# Sheet1.net
KiCad netlist of a schematic drawn in Altium Designer
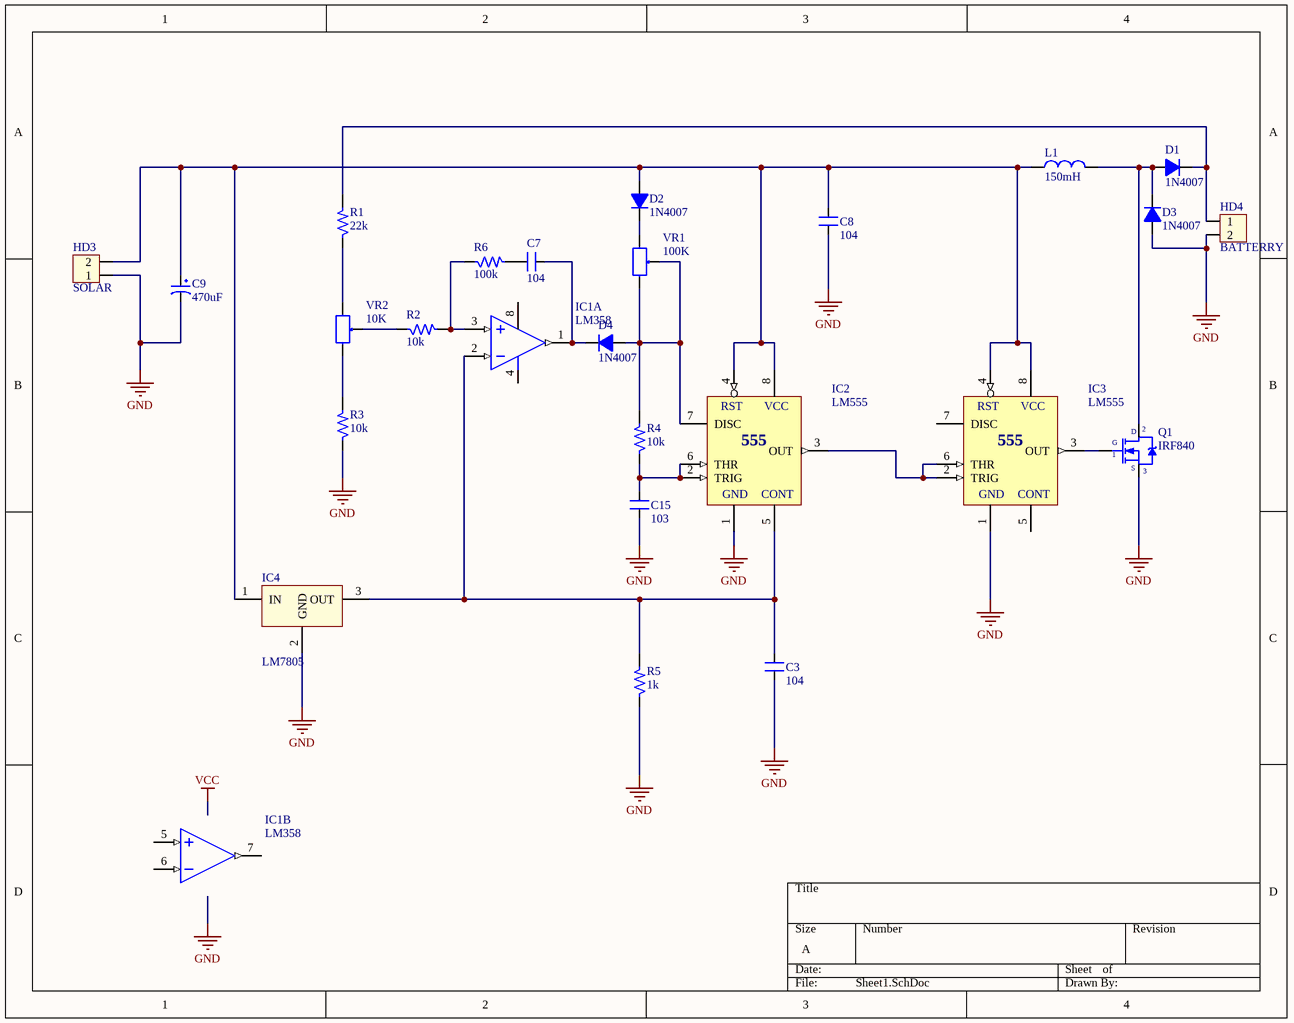
[diagram p0: Sheet1.SchDoc]

(export (version "E")
  (design (tool "Eeschema 10.0.6"))
  (components
    (comp (ref "C3")
      (value "104")
      (footprint "CN2")
      (description "Cap np 104 => 105pF")
      (libsource (lib "syhaunguyen") (part "CN2"))
    )
    (comp (ref "C7")
      (value "104")
      (footprint "CN1")
      (description "Cap np  1pF - 472pF")
      (libsource (lib "syhaunguyen") (part "CN1"))
    )
    (comp (ref "C8")
      (value "104")
      (footprint "CN1")
      (description "Cap np  1pF - 472pF")
      (libsource (lib "syhaunguyen") (part "CN1"))
    )
    (comp (ref "C9")
      (value "470uF")
      (footprint "CP1/2")
      (description "Cap P  0,1uF < 22uF , 16 - 50V")
      (libsource (lib "syhaunguyen") (part "CP1"))
    )
    (comp (ref "C15")
      (value "103")
      (footprint "CN1")
      (description "Cap np  1pF - 472pF")
      (libsource (lib "syhaunguyen") (part "CN1"))
    )
    (comp (ref "D1")
      (value "1N4007")
      (footprint "D1A")
      (description "Diode 1A")
      (libsource (lib "syhaunguyen") (part "D1A"))
    )
    (comp (ref "D2")
      (value "1N4007")
      (footprint "D1A")
      (description "Diode 1A")
      (libsource (lib "syhaunguyen") (part "D1A"))
    )
    (comp (ref "D3")
      (value "1N4007")
      (footprint "D1A")
      (description "Diode 1A")
      (libsource (lib "syhaunguyen") (part "D1A"))
    )
    (comp (ref "D4")
      (value "1N4007")
      (footprint "D1A")
      (description "Diode 1A")
      (libsource (lib "syhaunguyen") (part "D1A"))
    )
    (comp (ref "HD3")
      (value "SOLAR")
      (footprint "HED2")
      (description "Header 2 (Green)")
      (libsource (lib "syhaunguyen") (part "Hed2"))
    )
    (comp (ref "HD4")
      (value "BATTERRY")
      (footprint "HED2")
      (description "Header 2 (Green)")
      (libsource (lib "") (part "Hed2_1"))
    )
    (comp (ref "IC1")
      (value "LM358")
      (footprint "DIP8/W0.3")
      (description "Low-Power Dual Operational Amplifier")
      (libsource (lib "syhaunguyen") (part "LM358"))
    )
    (comp (ref "IC2")
      (value "LM555")
      (footprint "DIP8/W0.3")
      (description "Timer")
      (libsource (lib "syhaunguyen") (part "LM555"))
    )
    (comp (ref "IC3")
      (value "LM555")
      (footprint "DIP8/W0.3")
      (description "Timer")
      (libsource (lib "syhaunguyen") (part "LM555"))
    )
    (comp (ref "IC4")
      (value "LM7805")
      (footprint "QTO-220")
      (description "On ap +, from + 5 to + 24VDC")
      (libsource (lib "syhaunguyen") (part "LM78xx"))
    )
    (comp (ref "L1")
      (value "150mH")
      (footprint "L/0.4")
      (description "Inductor")
      (libsource (lib "syhaunguyen") (part "L1"))
    )
    (comp (ref "Q1")
      (value "IRF840")
      (footprint "QTO-220")
      (description "MOSFET N - CHANNEL 500V - 0.75 - 8A - TO-220")
      (libsource (lib "syhaunguyen") (part "IRF840"))
    )
    (comp (ref "R1")
      (value "22k")
      (footprint "SM-RES-1206")
      (description "Resistor 1/4W")
      (libsource (lib "syhaunguyen") (part "R"))
    )
    (comp (ref "R2")
      (value "10k")
      (footprint "SM-RES-1206")
      (description "Resistor 1/4W")
      (libsource (lib "syhaunguyen") (part "R"))
    )
    (comp (ref "R3")
      (value "10k")
      (footprint "SM-RES-1206")
      (description "Resistor 1/4W")
      (libsource (lib "syhaunguyen") (part "R"))
    )
    (comp (ref "R4")
      (value "10k")
      (footprint "SM-RES-1206")
      (description "Resistor 1/4W")
      (libsource (lib "syhaunguyen") (part "R"))
    )
    (comp (ref "R5")
      (value "1k")
      (footprint "SM-RES-1206")
      (description "Resistor 1/4W")
      (libsource (lib "syhaunguyen") (part "R"))
    )
    (comp (ref "R6")
      (value "100k")
      (footprint "SM-RES-1206")
      (description "Resistor 1/4W")
      (libsource (lib "syhaunguyen") (part "R"))
    )
    (comp (ref "VR1")
      (value "100K")
      (footprint "VR")
      (description "Var Resistor")
      (libsource (lib "syhaunguyen") (part "VR"))
    )
    (comp (ref "VR2")
      (value "10K")
      (footprint "VR")
      (description "Var Resistor")
      (libsource (lib "syhaunguyen") (part "VR"))
    )
  )
  (nets
    (net (code "1") (name "GND") (class "Default")
      (node (ref "C15") (pin "1") (pinfunction "1_1") (pintype "passive"))
      (node (ref "C3") (pin "1") (pinfunction "1_1") (pintype "passive"))
      (node (ref "C8") (pin "1") (pinfunction "1_1") (pintype "passive"))
      (node (ref "C9") (pin "2") (pinfunction "2_2") (pintype "passive"))
      (node (ref "D3") (pin "1") (pinfunction "A_1") (pintype "passive"))
      (node (ref "HD3") (pin "1") (pinfunction "1_1") (pintype "passive"))
      (node (ref "HD4") (pin "2") (pinfunction "2_2") (pintype "passive"))
      (node (ref "IC2") (pin "1") (pinfunction "GND_1") (pintype "power_in"))
      (node (ref "IC3") (pin "1") (pinfunction "GND_1") (pintype "power_in"))
      (node (ref "IC4") (pin "2") (pinfunction "GND_2") (pintype "passive"))
      (node (ref "Q1") (pin "3") (pinfunction "S_3") (pintype "passive"))
      (node (ref "R3") (pin "1") (pinfunction "1_1") (pintype "passive"))
      (node (ref "R5") (pin "1") (pinfunction "1_1") (pintype "passive"))
    )
    (net (code "2") (name "Net-(C7-Pad2)") (class "Default")
      (node (ref "C7") (pin "2") (pinfunction "2_2") (pintype "passive"))
      (node (ref "R6") (pin "2") (pinfunction "2_2") (pintype "passive"))
    )
    (net (code "3") (name "Net-(D1-A)") (class "Default")
      (node (ref "D1") (pin "1") (pinfunction "A_1") (pintype "passive"))
      (node (ref "D3") (pin "2") (pinfunction "K_2") (pintype "passive"))
      (node (ref "L1") (pin "2") (pinfunction "2_2") (pintype "passive"))
      (node (ref "Q1") (pin "2") (pinfunction "D_2") (pintype "passive"))
    )
    (net (code "4") (name "Net-(D1-K)") (class "Default")
      (node (ref "D1") (pin "2") (pinfunction "K_2") (pintype "passive"))
      (node (ref "HD4") (pin "1") (pinfunction "1_1") (pintype "passive"))
      (node (ref "R1") (pin "2") (pinfunction "2_2") (pintype "passive"))
    )
    (net (code "5") (name "Net-(D2-A)") (class "Default")
      (node (ref "C8") (pin "2") (pinfunction "2_2") (pintype "passive"))
      (node (ref "C9") (pin "1") (pinfunction "1_1") (pintype "passive"))
      (node (ref "D2") (pin "1") (pinfunction "A_1") (pintype "passive"))
      (node (ref "HD3") (pin "2") (pinfunction "2_2") (pintype "passive"))
      (node (ref "IC2") (pin "4") (pinfunction "RST_4") (pintype "input"))
      (node (ref "IC2") (pin "8") (pinfunction "VCC_8") (pintype "power_in"))
      (node (ref "IC3") (pin "4") (pinfunction "RST_4") (pintype "input"))
      (node (ref "IC3") (pin "8") (pinfunction "VCC_8") (pintype "power_in"))
      (node (ref "IC4") (pin "1") (pinfunction "IN_1") (pintype "passive"))
      (node (ref "L1") (pin "1") (pinfunction "1_1") (pintype "passive"))
    )
    (net (code "6") (name "Net-(D2-K)") (class "Default")
      (node (ref "D2") (pin "2") (pinfunction "K_2") (pintype "passive"))
      (node (ref "VR1") (pin "1") (pinfunction "1_1") (pintype "passive"))
    )
    (net (code "7") (name "Net-(D4-A)") (class "Default")
      (node (ref "D4") (pin "1") (pinfunction "A_1") (pintype "passive"))
      (node (ref "IC2") (pin "7") (pinfunction "DISC_7") (pintype "open_collector"))
      (node (ref "R4") (pin "2") (pinfunction "2_2") (pintype "passive"))
      (node (ref "VR1") (pin "2") (pinfunction "2_2") (pintype "passive"))
      (node (ref "VR1") (pin "3") (pinfunction "3_3") (pintype "passive"))
    )
    (net (code "8") (name "Net-(D4-K)") (class "Default")
      (node (ref "C7") (pin "1") (pinfunction "1_1") (pintype "passive"))
      (node (ref "D4") (pin "2") (pinfunction "K_2") (pintype "passive"))
      (node (ref "IC1") (pin "1") (pinfunction "OUT_1") (pintype "output"))
    )
    (net (code "9") (name "Net-(IC1A-IN+)") (class "Default")
      (node (ref "IC1") (pin "3") (pinfunction "IN+_3") (pintype "input"))
      (node (ref "R2") (pin "2") (pinfunction "2_2") (pintype "passive"))
      (node (ref "R6") (pin "1") (pinfunction "1_1") (pintype "passive"))
    )
    (net (code "10") (name "Net-(IC1A-IN-)") (class "Default")
      (node (ref "C3") (pin "2") (pinfunction "2_2") (pintype "passive"))
      (node (ref "IC1") (pin "2") (pinfunction "IN-_2") (pintype "input"))
      (node (ref "IC2") (pin "5") (pinfunction "CONT_5") (pintype "passive"))
      (node (ref "IC4") (pin "3") (pinfunction "OUT_3") (pintype "passive"))
      (node (ref "R5") (pin "2") (pinfunction "2_2") (pintype "passive"))
    )
    (net (code "11") (name "Net-(IC2-OUT)") (class "Default")
      (node (ref "IC2") (pin "3") (pinfunction "OUT_3") (pintype "output"))
      (node (ref "IC3") (pin "2") (pinfunction "TRIG_2") (pintype "input"))
      (node (ref "IC3") (pin "6") (pinfunction "THR_6") (pintype "input"))
    )
    (net (code "12") (name "Net-(IC2-THR)") (class "Default")
      (node (ref "C15") (pin "2") (pinfunction "2_2") (pintype "passive"))
      (node (ref "IC2") (pin "2") (pinfunction "TRIG_2") (pintype "input"))
      (node (ref "IC2") (pin "6") (pinfunction "THR_6") (pintype "input"))
      (node (ref "R4") (pin "1") (pinfunction "1_1") (pintype "passive"))
    )
    (net (code "13") (name "Net-(IC3-OUT)") (class "Default")
      (node (ref "IC3") (pin "3") (pinfunction "OUT_3") (pintype "output"))
      (node (ref "Q1") (pin "1") (pinfunction "G_1") (pintype "passive"))
    )
    (net (code "14") (name "Net-(R1-Pad1)") (class "Default")
      (node (ref "R1") (pin "1") (pinfunction "1_1") (pintype "passive"))
      (node (ref "VR2") (pin "1") (pinfunction "1_1") (pintype "passive"))
    )
    (net (code "15") (name "Net-(R2-Pad1)") (class "Default")
      (node (ref "R2") (pin "1") (pinfunction "1_1") (pintype "passive"))
      (node (ref "VR2") (pin "2") (pinfunction "2_2") (pintype "passive"))
    )
    (net (code "16") (name "Net-(R3-Pad2)") (class "Default")
      (node (ref "R3") (pin "2") (pinfunction "2_2") (pintype "passive"))
      (node (ref "VR2") (pin "3") (pinfunction "3_3") (pintype "passive"))
    )
    (net (code "18") (name "unconnected-(IC1A-+V-Pad8)") (class "Default")
      (node (ref "IC1") (pin "8") (pinfunction "+V_8") (pintype "passive"))
    )
    (net (code "19") (name "unconnected-(IC1A--V-Pad4)") (class "Default")
      (node (ref "IC1") (pin "4") (pinfunction "-V_4") (pintype "passive"))
    )
    (net (code "20") (name "unconnected-(IC1B-IN+-Pad5)") (class "Default")
      (node (ref "IC1") (pin "5") (pinfunction "IN+_5") (pintype "input"))
    )
    (net (code "21") (name "unconnected-(IC1B-IN--Pad6)") (class "Default")
      (node (ref "IC1") (pin "6") (pinfunction "IN-_6") (pintype "input"))
    )
    (net (code "22") (name "unconnected-(IC1B-OUT-Pad7)") (class "Default")
      (node (ref "IC1") (pin "7") (pinfunction "OUT_7") (pintype "output"))
    )
    (net (code "23") (name "unconnected-(IC3-CONT-Pad5)") (class "Default")
      (node (ref "IC3") (pin "5") (pinfunction "CONT_5") (pintype "passive"))
    )
    (net (code "24") (name "unconnected-(IC3-DISC-Pad7)") (class "Default")
      (node (ref "IC3") (pin "7") (pinfunction "DISC_7") (pintype "open_collector"))
    )
  )
)
